# KS2E-IMD-AMS-LATCH.net
KiCad netlist of a schematic drawn in Altium Designer
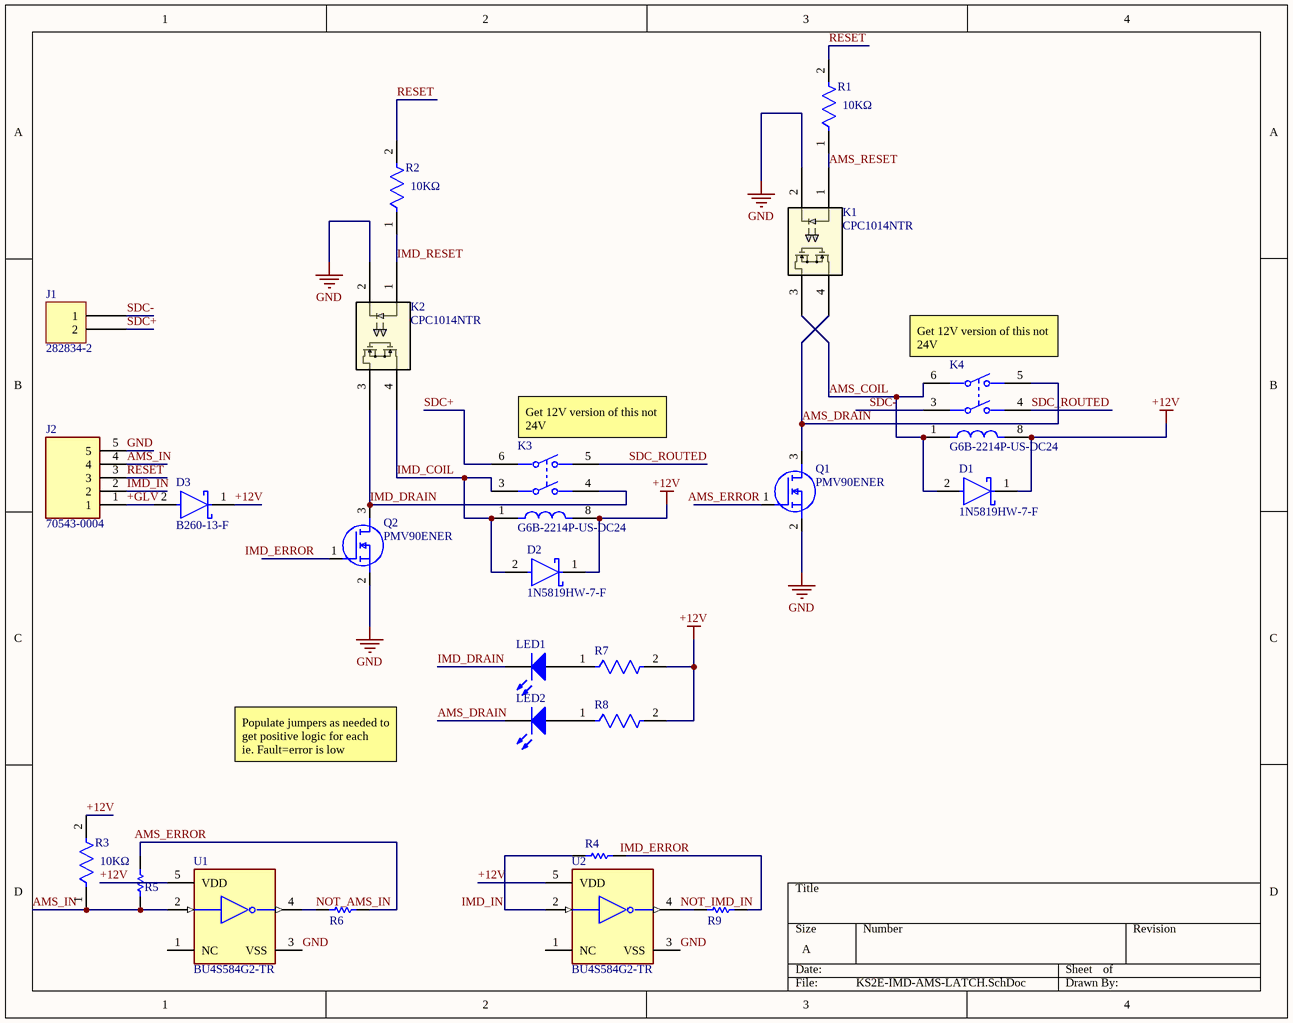
[diagram p0: KS2E-IMD-AMS-LATCH.SchDoc]

(export (version "E")
  (design (tool "Eeschema 10.0.6"))
  (components
    (comp (ref "D1")
      (value "1N5819HW-7-F")
      (footprint "FP-SOD123-IPC_A")
      (description "DIODE SCHOTTKY 40V 1A SOD123")
      (libsource (lib "Altium Content Vault") (part "1d6ec82d83fb6aee721767c19dac4b9"))
    )
    (comp (ref "D2")
      (value "1N5819HW-7-F")
      (footprint "FP-SOD123-IPC_A")
      (description "DIODE SCHOTTKY 40V 1A SOD123")
      (libsource (lib "Altium Content Vault") (part "1d6ec82d83fb6aee721767c19dac4b9"))
    )
    (comp (ref "D3")
      (value "B260-13-F")
      (footprint "FP-SMB-MFG")
      (description "DIODE SCHOTTKY 60V 2A SMB")
      (fields
        (field (name "MANUFACTURER") "Diodes Inc.")
        (field (name "OCTOPART") "https://octopart.com/b260-13-f-diodes+inc.-325789")
      )
      (libsource (lib "Altium Content Vault") (part "1d6ec82d83fb6aee721767c19dac4b9"))
    )
    (comp (ref "J1")
      (value "282834-2")
      (footprint "TE 282834-2")
      (description "TERM BLK 2P SIDE ENT 2.54MM PCB")
      (fields (field (name "MANUFACTURER") "TE Connectivity AMP Connectors") (field (name "VOLTAGE") "150V"))
      (libsource (lib "Celestial Altium Library - altium_library") (part "2 Pin"))
    )
    (comp (ref "J2")
      (value "70543-0004")
      (footprint "SamacSys:SHDR5W64P0X254_1X5_1525X660X1181P")
      (description "Connector")
      (fields (field (name "MOUSER PART NUMBER") "538-70543-0004"))
      (libsource (lib "*") (part "70543-0004"))
    )
    (comp (ref "K1")
      (value "CPC1014NTR")
      (footprint "CPC1014N_IXY")
      (description "No Description Available")
      (fields (field (name "COPYRIGHT") "Copyright (C) 2022 Ultra Librarian. All rights reserved."))
      (libsource (lib "CPC1014NTR") (part "CPC1014NTR"))
    )
    (comp (ref "K2")
      (value "CPC1014NTR")
      (footprint "CPC1014N_IXY")
      (description "No Description Available")
      (fields (field (name "COPYRIGHT") "Copyright (C) 2022 Ultra Librarian. All rights reserved."))
      (libsource (lib "CPC1014NTR") (part "CPC1014NTR"))
    )
    (comp (ref "K3")
      (value "G6B-2214P-US-DC24")
      (footprint "FP-G6B-2214P-US-DC24-MFG")
      (description "RELAY GEN PURPOSE DPST 5A 24V")
      (libsource (lib "Altium Content Vault") (part "3091bf9be4901fb129b6814a508a03d"))
    )
    (comp (ref "K4")
      (value "G6B-2214P-US-DC24")
      (footprint "FP-G6B-2214P-US-DC24-MFG")
      (description "RELAY GEN PURPOSE DPST 5A 24V")
      (libsource (lib "Altium Content Vault") (part "3091bf9be4901fb129b6814a508a03d"))
    )
    (comp (ref "LED1")
      (value "150080SS75000")
      (footprint "0805_A")
      (description "SMD mono-color Chip LED, WL-SMCW, Super Red")
      (fields (field (name "MANUFACTURER") "Wuerth Elektronik"))
      (libsource (lib "Altium Content Vault") (part "WE-LED_K1A2-2"))
    )
    (comp (ref "LED2")
      (value "150080SS75000")
      (footprint "0805_A")
      (description "SMD mono-color Chip LED, WL-SMCW, Super Red")
      (fields (field (name "MANUFACTURER") "Wuerth Elektronik"))
      (libsource (lib "Altium Content Vault") (part "WE-LED_K1A2-2"))
    )
    (comp (ref "Q1")
      (value "PMV90ENER")
      (footprint "SamacSys:SOT95P230X110-3N")
      (description "MOSFET (N-Channel)")
      (fields (field (name "MOUSER PART NUMBER") "771-PMV90ENER"))
      (libsource (lib "*") (part "PMV90ENER"))
    )
    (comp (ref "Q2")
      (value "PMV90ENER")
      (footprint "SamacSys:SOT95P230X110-3N")
      (description "MOSFET (N-Channel)")
      (fields (field (name "MOUSER PART NUMBER") "771-PMV90ENER"))
      (libsource (lib "*") (part "PMV90ENER"))
    )
    (comp (ref "R1")
      (value "RP73PF2A10KBTDF")
      (footprint "FP-RP73P-2A-MFG")
      (description "RP73P 0805 10KΩ 0.25W 25ppm/°C 0.10% 150V")
      (fields
        (field (name "MANUFACTURER") "TE Connectivity")
        (field (name "TOLERANCE") "0.001")
        (field (name "RESISTANCE") "10KΩ")
      )
      (libsource (lib "Altium Content Vault") (part "1029c3af85768c4190bb7ad29bc67b5"))
    )
    (comp (ref "R2")
      (value "RP73PF2A10KBTDF")
      (footprint "FP-RP73P-2A-MFG")
      (description "RP73P 0805 10KΩ 0.25W 25ppm/°C 0.10% 150V")
      (fields
        (field (name "MANUFACTURER") "TE Connectivity")
        (field (name "TOLERANCE") "0.001")
        (field (name "RESISTANCE") "10KΩ")
      )
      (libsource (lib "Altium Content Vault") (part "1029c3af85768c4190bb7ad29bc67b5"))
    )
    (comp (ref "R3")
      (value "RP73PF2A10KBTDF")
      (footprint "FP-RP73P-2A-MFG")
      (description "RP73P 0805 10KΩ 0.25W 25ppm/°C 0.10% 150V")
      (fields
        (field (name "MANUFACTURER") "TE Connectivity")
        (field (name "TOLERANCE") "0.001")
        (field (name "RESISTANCE") "10KΩ")
      )
      (libsource (lib "Altium Content Vault") (part "1029c3af85768c4190bb7ad29bc67b5"))
    )
    (comp (ref "R4")
      (value "CRG0805ZR")
      (footprint "RESC2013X65X40LL15T20")
      (description "Chip Resistor, 0 Ohm, 0.125 W, -55 to 125 degC, 0805 (2012 Metric), RoHS, Tape and Reel")
      (fields (field (name "TOLERANCE") "0%") (field (name "MANUFACTURER") "TE Connectivity"))
      (libsource (lib "Altium Content Vault") (part "RES-2"))
    )
    (comp (ref "R5")
      (value "CRG0805ZR")
      (footprint "RESC2013X65X40LL15T20")
      (description "Chip Resistor, 0 Ohm, 0.125 W, -55 to 125 degC, 0805 (2012 Metric), RoHS, Tape and Reel")
      (fields (field (name "TOLERANCE") "0%") (field (name "MANUFACTURER") "TE Connectivity"))
      (libsource (lib "Altium Content Vault") (part "RES-2"))
    )
    (comp (ref "R6")
      (value "CRG0805ZR")
      (footprint "RESC2013X65X40LL15T20")
      (description "Chip Resistor, 0 Ohm, 0.125 W, -55 to 125 degC, 0805 (2012 Metric), RoHS, Tape and Reel")
      (fields (field (name "TOLERANCE") "0%") (field (name "MANUFACTURER") "TE Connectivity"))
      (libsource (lib "Altium Content Vault") (part "RES-2"))
    )
    (comp (ref "R7")
      (value "CRCW1206500RJNEA")
      (footprint "FP-CRCW1206-e3-IPC_B")
      (description "RES Thick Film, 500Ω, 5%, 0.25W, 200ppm/°C, 1206")
      (fields (field (name "TOLERANCE") "5%"))
      (libsource (lib "Altium Content Vault") (part "1029c3af85768c4190bb7ad29bc67b5"))
    )
    (comp (ref "R8")
      (value "CRCW1206500RJNEA")
      (footprint "FP-CRCW1206-e3-IPC_B")
      (description "RES Thick Film, 500Ω, 5%, 0.25W, 200ppm/°C, 1206")
      (fields (field (name "TOLERANCE") "5%"))
      (libsource (lib "Altium Content Vault") (part "1029c3af85768c4190bb7ad29bc67b5"))
    )
    (comp (ref "R9")
      (value "CRG0805ZR")
      (footprint "RESC2013X65X40LL15T20")
      (description "Chip Resistor, 0 Ohm, 0.125 W, -55 to 125 degC, 0805 (2012 Metric), RoHS, Tape and Reel")
      (fields (field (name "TOLERANCE") "0%") (field (name "MANUFACTURER") "TE Connectivity"))
      (libsource (lib "Altium Content Vault") (part "RES-2"))
    )
    (comp (ref "U1")
      (value "BU4S584G2-TR")
      (footprint "FP-SSOP5-MFG")
      (description "Inverters IC SCHMITT TRIGGER SINGLE")
      (fields (field (name "OCTOPART") "https://octopart.com/bu4s584g2-tr-rohm-466637"))
      (libsource (lib "Altium Content Vault") (part "0f0365dab255d65fcc0045caa630606"))
    )
    (comp (ref "U2")
      (value "BU4S584G2-TR")
      (footprint "FP-SSOP5-MFG")
      (description "Inverters IC SCHMITT TRIGGER SINGLE")
      (fields (field (name "OCTOPART") "https://octopart.com/bu4s584g2-tr-rohm-466637"))
      (libsource (lib "Altium Content Vault") (part "0f0365dab255d65fcc0045caa630606"))
    )
  )
  (nets
    (net (code "1") (name "+12V") (class "Default")
      (node (ref "D1") (pin "1") (pinfunction "C_1") (pintype "passive"))
      (node (ref "D2") (pin "1") (pinfunction "C_1") (pintype "passive"))
      (node (ref "D3") (pin "1") (pinfunction "C_1") (pintype "passive"))
      (node (ref "K3") (pin "8") (pinfunction "8_8") (pintype "passive"))
      (node (ref "K4") (pin "8") (pinfunction "8_8") (pintype "passive"))
      (node (ref "R3") (pin "2") (pinfunction "2_2") (pintype "passive"))
      (node (ref "R7") (pin "2") (pinfunction "2_2") (pintype "passive"))
      (node (ref "R8") (pin "2") (pinfunction "2_2") (pintype "passive"))
      (node (ref "U1") (pin "5") (pinfunction "VDD_5") (pintype "power_in"))
      (node (ref "U2") (pin "5") (pinfunction "VDD_5") (pintype "power_in"))
    )
    (net (code "2") (name "/+GLV") (class "Default")
      (node (ref "D3") (pin "2") (pinfunction "A_2") (pintype "passive"))
      (node (ref "J2") (pin "1") (pinfunction "1_1") (pintype "passive"))
    )
    (net (code "3") (name "/AMS_COIL") (class "Default")
      (node (ref "D1") (pin "2") (pinfunction "A_2") (pintype "passive"))
      (node (ref "K1") (pin "3") (pinfunction "3_3") (pintype "passive"))
      (node (ref "K4") (pin "1") (pinfunction "1_1") (pintype "passive"))
      (node (ref "K4") (pin "6") (pinfunction "6_6") (pintype "passive"))
    )
    (net (code "4") (name "/AMS_DRAIN") (class "Default")
      (node (ref "K1") (pin "4") (pinfunction "4_4") (pintype "passive"))
      (node (ref "K4") (pin "5") (pinfunction "5_5") (pintype "passive"))
      (node (ref "LED2") (pin "1") (pinfunction "K_1") (pintype "passive"))
      (node (ref "Q1") (pin "3") (pinfunction "D_3") (pintype "passive"))
    )
    (net (code "5") (name "/AMS_ERROR") (class "Default")
      (node (ref "Q1") (pin "1") (pinfunction "G_1") (pintype "passive"))
      (node (ref "R5") (pin "2") (pinfunction "2_2") (pintype "passive"))
      (node (ref "R6") (pin "2") (pinfunction "2_2") (pintype "passive"))
    )
    (net (code "6") (name "/AMS_IN") (class "Default")
      (node (ref "J2") (pin "4") (pinfunction "4_4") (pintype "passive"))
      (node (ref "R3") (pin "1") (pinfunction "1_1") (pintype "passive"))
      (node (ref "R5") (pin "1") (pinfunction "1_1") (pintype "passive"))
      (node (ref "U1") (pin "2") (pinfunction "A_2") (pintype "input"))
    )
    (net (code "7") (name "/AMS_RESET") (class "Default")
      (node (ref "K1") (pin "1") (pinfunction "1_1") (pintype "passive"))
      (node (ref "R1") (pin "1") (pinfunction "1_1") (pintype "passive"))
    )
    (net (code "8") (name "/IMD_COIL") (class "Default")
      (node (ref "D2") (pin "2") (pinfunction "A_2") (pintype "passive"))
      (node (ref "K2") (pin "4") (pinfunction "4_4") (pintype "passive"))
      (node (ref "K3") (pin "1") (pinfunction "1_1") (pintype "passive"))
      (node (ref "K3") (pin "3") (pinfunction "3_3") (pintype "passive"))
    )
    (net (code "9") (name "/IMD_DRAIN") (class "Default")
      (node (ref "K2") (pin "3") (pinfunction "3_3") (pintype "passive"))
      (node (ref "K3") (pin "4") (pinfunction "4_4") (pintype "passive"))
      (node (ref "LED1") (pin "1") (pinfunction "K_1") (pintype "passive"))
      (node (ref "Q2") (pin "3") (pinfunction "D_3") (pintype "passive"))
    )
    (net (code "10") (name "/IMD_ERROR") (class "Default")
      (node (ref "Q2") (pin "1") (pinfunction "G_1") (pintype "passive"))
      (node (ref "R4") (pin "2") (pinfunction "2_2") (pintype "passive"))
      (node (ref "R9") (pin "2") (pinfunction "2_2") (pintype "passive"))
    )
    (net (code "11") (name "/IMD_IN") (class "Default")
      (node (ref "J2") (pin "2") (pinfunction "2_2") (pintype "passive"))
      (node (ref "R4") (pin "1") (pinfunction "1_1") (pintype "passive"))
      (node (ref "U2") (pin "2") (pinfunction "A_2") (pintype "input"))
    )
    (net (code "12") (name "/IMD_RESET") (class "Default")
      (node (ref "K2") (pin "1") (pinfunction "1_1") (pintype "passive"))
      (node (ref "R2") (pin "1") (pinfunction "1_1") (pintype "passive"))
    )
    (net (code "13") (name "/NOT_AMS_IN") (class "Default")
      (node (ref "R6") (pin "1") (pinfunction "1_1") (pintype "passive"))
      (node (ref "U1") (pin "4") (pinfunction "Y_4") (pintype "output"))
    )
    (net (code "14") (name "/NOT_IMD_IN") (class "Default")
      (node (ref "R9") (pin "1") (pinfunction "1_1") (pintype "passive"))
      (node (ref "U2") (pin "4") (pinfunction "Y_4") (pintype "output"))
    )
    (net (code "15") (name "/RESET") (class "Default")
      (node (ref "J2") (pin "3") (pinfunction "3_3") (pintype "passive"))
      (node (ref "R1") (pin "2") (pinfunction "2_2") (pintype "passive"))
      (node (ref "R2") (pin "2") (pinfunction "2_2") (pintype "passive"))
    )
    (net (code "16") (name "/SDC+") (class "Default")
      (node (ref "J1") (pin "2") (pinfunction "2_2") (pintype "passive"))
      (node (ref "K3") (pin "6") (pinfunction "6_6") (pintype "passive"))
    )
    (net (code "17") (name "/SDC-") (class "Default")
      (node (ref "J1") (pin "1") (pinfunction "1_1") (pintype "passive"))
      (node (ref "K4") (pin "3") (pinfunction "3_3") (pintype "passive"))
    )
    (net (code "18") (name "/SDC_ROUTED") (class "Default")
      (node (ref "K3") (pin "5") (pinfunction "5_5") (pintype "passive"))
      (node (ref "K4") (pin "4") (pinfunction "4_4") (pintype "passive"))
    )
    (net (code "19") (name "GND") (class "Default")
      (node (ref "J2") (pin "5") (pinfunction "5_5") (pintype "passive"))
      (node (ref "K1") (pin "2") (pinfunction "2_2") (pintype "passive"))
      (node (ref "K2") (pin "2") (pinfunction "2_2") (pintype "passive"))
      (node (ref "Q1") (pin "2") (pinfunction "S_2") (pintype "passive"))
      (node (ref "Q2") (pin "2") (pinfunction "S_2") (pintype "passive"))
      (node (ref "U1") (pin "3") (pinfunction "VSS_3") (pintype "power_in"))
      (node (ref "U2") (pin "3") (pinfunction "VSS_3") (pintype "power_in"))
    )
    (net (code "20") (name "Net-(LED1-A)") (class "Default")
      (node (ref "LED1") (pin "2") (pinfunction "A_2") (pintype "passive"))
      (node (ref "R7") (pin "1") (pinfunction "1_1") (pintype "passive"))
    )
    (net (code "21") (name "Net-(LED2-A)") (class "Default")
      (node (ref "LED2") (pin "2") (pinfunction "A_2") (pintype "passive"))
      (node (ref "R8") (pin "1") (pinfunction "1_1") (pintype "passive"))
    )
    (net (code "22") (name "unconnected-(U1-NC-Pad1)") (class "Default")
      (node (ref "U1") (pin "1") (pinfunction "NC_1") (pintype "passive"))
    )
    (net (code "23") (name "unconnected-(U2-NC-Pad1)") (class "Default")
      (node (ref "U2") (pin "1") (pinfunction "NC_1") (pintype "passive"))
    )
  )
)
